# WeMos32Buttons.net
KiCad netlist of a schematic drawn in EAGLE
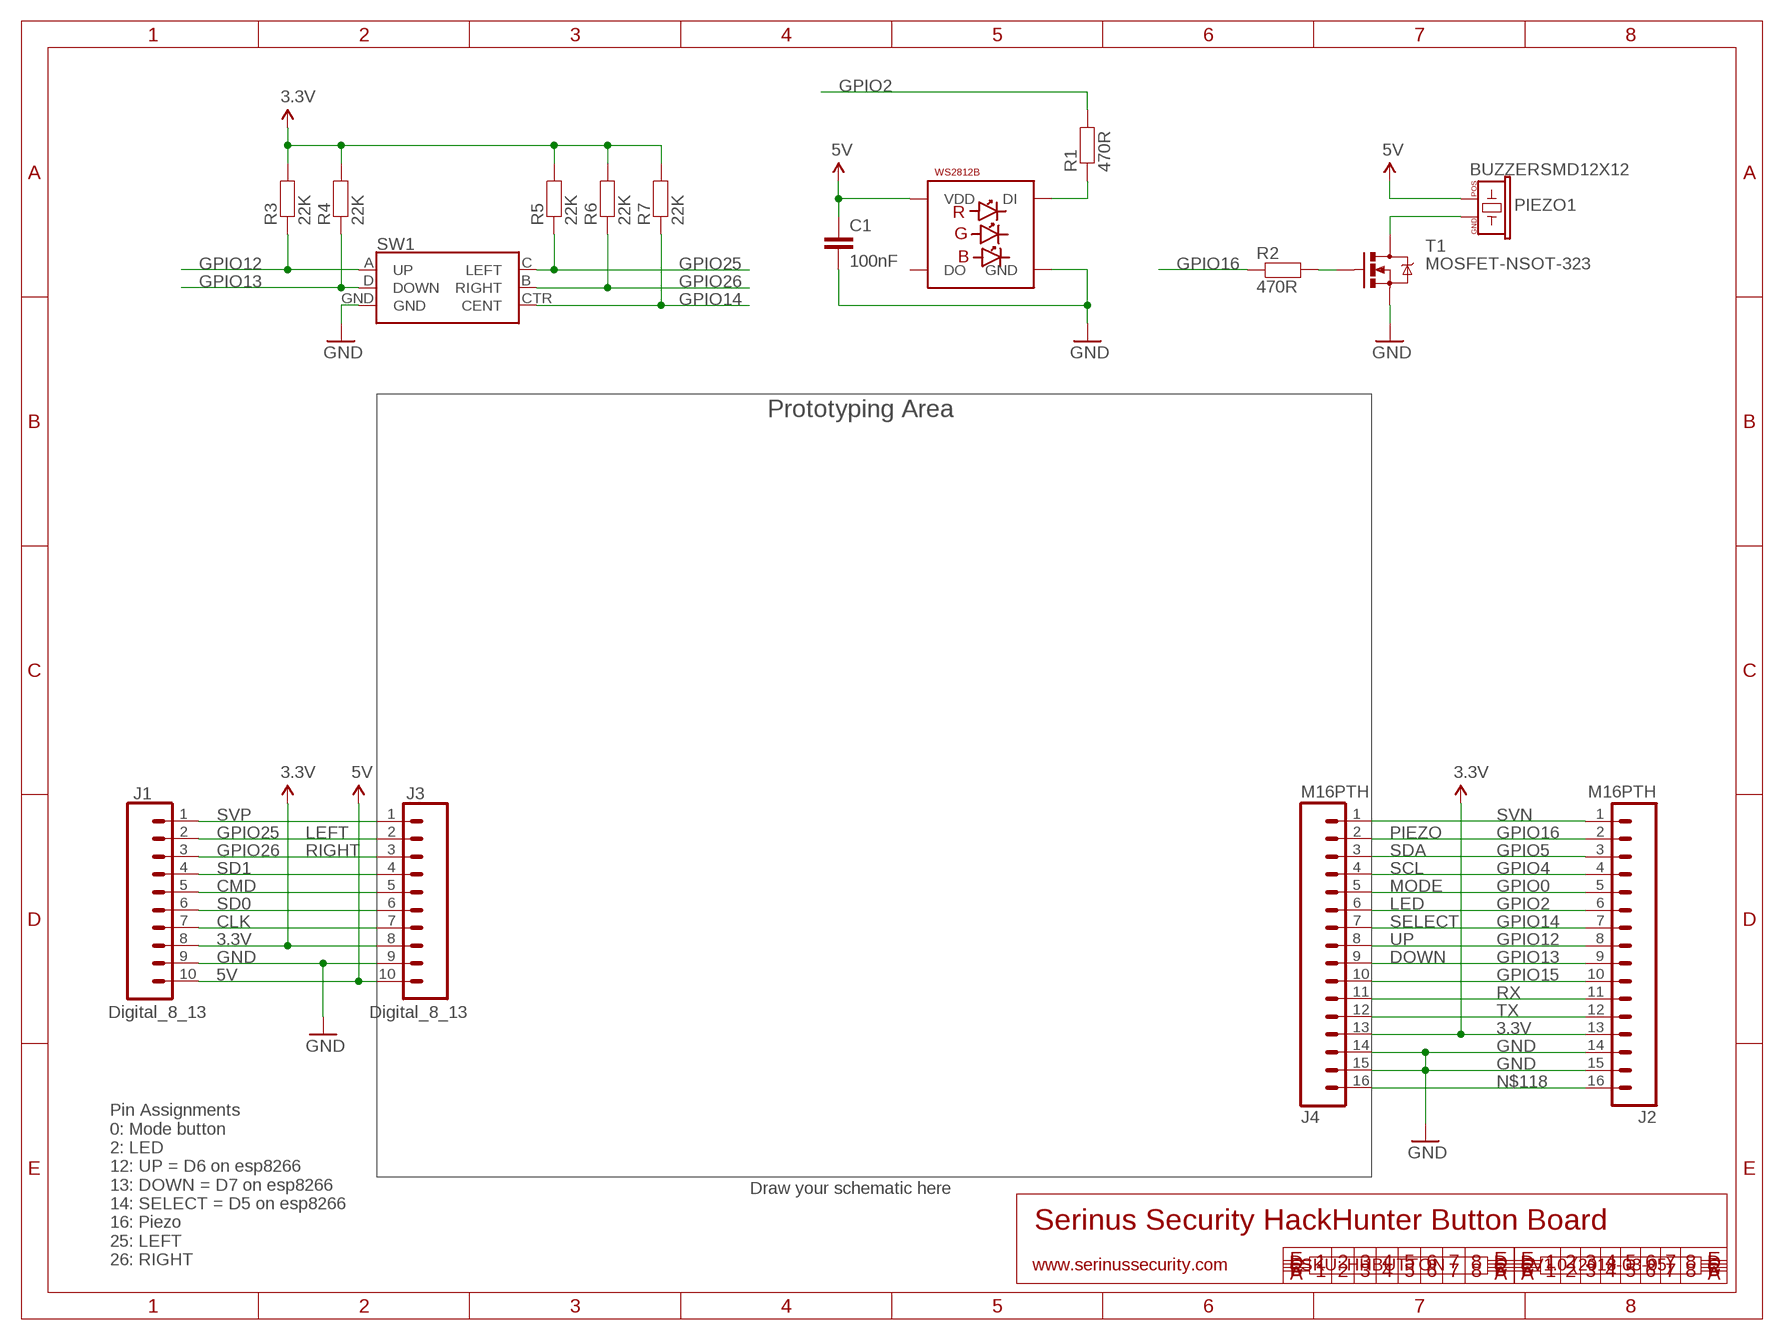
[diagram p0: schematic, sheet 1]

(export (version "E")
  (design (tool "Eeschema 10.0.6"))
  (components
    (comp (ref "C1")
      (value "100nF")
      (footprint "eagle-import:0603")
      (libsource (lib "eagle-import") (part "CAP0603"))
    )
    (comp (ref "J1")
      (value "Digital_8_13")
      (footprint "eagle-import:1X10")
      (libsource (lib "eagle-import") (part "M100.1"))
    )
    (comp (ref "J2")
      (value "M16PTH")
      (footprint "eagle-import:1X16")
      (libsource (lib "eagle-import") (part "M16PTH"))
    )
    (comp (ref "J3")
      (value "Digital_8_13")
      (footprint "eagle-import:1X10")
      (libsource (lib "eagle-import") (part "M100.1"))
    )
    (comp (ref "J4")
      (value "M16PTH")
      (footprint "eagle-import:1X16")
      (libsource (lib "eagle-import") (part "M16PTH"))
    )
    (comp (ref "LED2")
      (value "WS2812B5050")
      (footprint "eagle-import:WS2812B")
      (libsource (lib "eagle-import") (part "WS2812B5050"))
    )
    (comp (ref "PIEZO1")
      (value "BUZZERSMD12X12")
      (footprint "eagle-import:BUZZER-12X12-SMT")
      (libsource (lib "eagle-import") (part "BUZZERSMD12X12"))
    )
    (comp (ref "R1")
      (value "470R")
      (footprint "eagle-import:0603")
      (libsource (lib "eagle-import") (part "RESISTOR0603"))
    )
    (comp (ref "R2")
      (value "470R")
      (footprint "eagle-import:0603")
      (libsource (lib "eagle-import") (part "RESISTOR0603"))
    )
    (comp (ref "R3")
      (value "22K")
      (footprint "eagle-import:0603")
      (libsource (lib "eagle-import") (part "RESISTOR0603"))
    )
    (comp (ref "R4")
      (value "22K")
      (footprint "eagle-import:0603")
      (libsource (lib "eagle-import") (part "RESISTOR0603"))
    )
    (comp (ref "R5")
      (value "22K")
      (footprint "eagle-import:0603")
      (libsource (lib "eagle-import") (part "RESISTOR0603"))
    )
    (comp (ref "R6")
      (value "22K")
      (footprint "eagle-import:0603")
      (libsource (lib "eagle-import") (part "RESISTOR0603"))
    )
    (comp (ref "R7")
      (value "22K")
      (footprint "eagle-import:0603")
      (libsource (lib "eagle-import") (part "RESISTOR0603"))
    )
    (comp (ref "SW1")
      (value "JOYSTICK_MINI")
      (footprint "eagle-import:JOYSTICK_MINI")
      (libsource (lib "eagle-import") (part "JOYSTICK_MINI"))
    )
    (comp (ref "T1")
      (value "MOSFET-NSOT-323")
      (footprint "eagle-import:SOT32-3")
      (libsource (lib "eagle-import") (part "MOSFET-NSOT-323"))
    )
  )
  (nets
    (net (code "1") (name "/CLK") (class "Default")
      (node (ref "J1") (pin "7") (pinfunction "7_7") (pintype "passive"))
      (node (ref "J3") (pin "7") (pinfunction "7_7") (pintype "passive"))
    )
    (net (code "2") (name "/CMD") (class "Default")
      (node (ref "J1") (pin "5") (pinfunction "5_5") (pintype "passive"))
      (node (ref "J3") (pin "5") (pinfunction "5_5") (pintype "passive"))
    )
    (net (code "3") (name "/GPIO0") (class "Default")
      (node (ref "J2") (pin "5") (pinfunction "5_5") (pintype "passive"))
      (node (ref "J4") (pin "5") (pinfunction "5_5") (pintype "passive"))
    )
    (net (code "4") (name "/GPIO2") (class "Default")
      (node (ref "J2") (pin "6") (pinfunction "6_6") (pintype "passive"))
      (node (ref "J4") (pin "6") (pinfunction "6_6") (pintype "passive"))
      (node (ref "R1") (pin "2") (pinfunction "2_2") (pintype "passive"))
    )
    (net (code "5") (name "/GPIO4") (class "Default")
      (node (ref "J2") (pin "4") (pinfunction "4_4") (pintype "passive"))
      (node (ref "J4") (pin "4") (pinfunction "4_4") (pintype "passive"))
    )
    (net (code "6") (name "/GPIO5") (class "Default")
      (node (ref "J2") (pin "3") (pinfunction "3_3") (pintype "passive"))
      (node (ref "J4") (pin "3") (pinfunction "3_3") (pintype "passive"))
    )
    (net (code "7") (name "/GPIO12") (class "Default")
      (node (ref "J2") (pin "8") (pinfunction "8_8") (pintype "passive"))
      (node (ref "J4") (pin "8") (pinfunction "8_8") (pintype "passive"))
      (node (ref "R3") (pin "1") (pinfunction "1_1") (pintype "passive"))
      (node (ref "SW1") (pin "A") (pinfunction "UP_A") (pintype "bidirectional"))
    )
    (net (code "8") (name "/GPIO13") (class "Default")
      (node (ref "J2") (pin "9") (pinfunction "9_9") (pintype "passive"))
      (node (ref "J4") (pin "9") (pinfunction "9_9") (pintype "passive"))
      (node (ref "R4") (pin "1") (pinfunction "1_1") (pintype "passive"))
      (node (ref "SW1") (pin "D") (pinfunction "DOWN_D") (pintype "bidirectional"))
    )
    (net (code "9") (name "/GPIO14") (class "Default")
      (node (ref "J2") (pin "7") (pinfunction "7_7") (pintype "passive"))
      (node (ref "J4") (pin "7") (pinfunction "7_7") (pintype "passive"))
      (node (ref "R7") (pin "1") (pinfunction "1_1") (pintype "passive"))
      (node (ref "SW1") (pin "CTR") (pinfunction "CENT_CTR") (pintype "bidirectional"))
    )
    (net (code "10") (name "/GPIO15") (class "Default")
      (node (ref "J2") (pin "10") (pinfunction "10_10") (pintype "passive"))
      (node (ref "J4") (pin "10") (pinfunction "10_10") (pintype "passive"))
    )
    (net (code "11") (name "/GPIO16") (class "Default")
      (node (ref "J2") (pin "2") (pinfunction "2_2") (pintype "passive"))
      (node (ref "J4") (pin "2") (pinfunction "2_2") (pintype "passive"))
      (node (ref "R2") (pin "1") (pinfunction "1_1") (pintype "passive"))
    )
    (net (code "12") (name "/GPIO25") (class "Default")
      (node (ref "J1") (pin "2") (pinfunction "2_2") (pintype "passive"))
      (node (ref "J3") (pin "2") (pinfunction "2_2") (pintype "passive"))
      (node (ref "R5") (pin "1") (pinfunction "1_1") (pintype "passive"))
      (node (ref "SW1") (pin "C") (pinfunction "LEFT_C") (pintype "bidirectional"))
    )
    (net (code "13") (name "/GPIO26") (class "Default")
      (node (ref "J1") (pin "3") (pinfunction "3_3") (pintype "passive"))
      (node (ref "J3") (pin "3") (pinfunction "3_3") (pintype "passive"))
      (node (ref "R6") (pin "1") (pinfunction "1_1") (pintype "passive"))
      (node (ref "SW1") (pin "B") (pinfunction "RIGHT_B") (pintype "bidirectional"))
    )
    (net (code "14") (name "/N$118") (class "Default")
      (node (ref "J2") (pin "16") (pinfunction "16_16") (pintype "passive"))
      (node (ref "J4") (pin "16") (pinfunction "16_16") (pintype "passive"))
    )
    (net (code "15") (name "/RX") (class "Default")
      (node (ref "J2") (pin "11") (pinfunction "11_11") (pintype "passive"))
      (node (ref "J4") (pin "11") (pinfunction "11_11") (pintype "passive"))
    )
    (net (code "16") (name "/SD0") (class "Default")
      (node (ref "J1") (pin "6") (pinfunction "6_6") (pintype "passive"))
      (node (ref "J3") (pin "6") (pinfunction "6_6") (pintype "passive"))
    )
    (net (code "17") (name "/SD1") (class "Default")
      (node (ref "J1") (pin "4") (pinfunction "4_4") (pintype "passive"))
      (node (ref "J3") (pin "4") (pinfunction "4_4") (pintype "passive"))
    )
    (net (code "18") (name "/SVN") (class "Default")
      (node (ref "J2") (pin "1") (pinfunction "1_1") (pintype "passive"))
      (node (ref "J4") (pin "1") (pinfunction "1_1") (pintype "passive"))
    )
    (net (code "19") (name "/SVP") (class "Default")
      (node (ref "J1") (pin "1") (pinfunction "1_1") (pintype "passive"))
      (node (ref "J3") (pin "1") (pinfunction "1_1") (pintype "passive"))
    )
    (net (code "20") (name "/TX") (class "Default")
      (node (ref "J2") (pin "12") (pinfunction "12_12") (pintype "passive"))
      (node (ref "J4") (pin "12") (pinfunction "12_12") (pintype "passive"))
    )
    (net (code "21") (name "3.3V") (class "Default")
      (node (ref "J1") (pin "8") (pinfunction "8_8") (pintype "passive"))
      (node (ref "J2") (pin "13") (pinfunction "13_13") (pintype "passive"))
      (node (ref "J3") (pin "8") (pinfunction "8_8") (pintype "passive"))
      (node (ref "J4") (pin "13") (pinfunction "13_13") (pintype "passive"))
      (node (ref "R3") (pin "2") (pinfunction "2_2") (pintype "passive"))
      (node (ref "R4") (pin "2") (pinfunction "2_2") (pintype "passive"))
      (node (ref "R5") (pin "2") (pinfunction "2_2") (pintype "passive"))
      (node (ref "R6") (pin "2") (pinfunction "2_2") (pintype "passive"))
      (node (ref "R7") (pin "2") (pinfunction "2_2") (pintype "passive"))
    )
    (net (code "22") (name "5V") (class "Default")
      (node (ref "C1") (pin "1") (pinfunction "1_1") (pintype "passive"))
      (node (ref "J1") (pin "10") (pinfunction "10_10") (pintype "passive"))
      (node (ref "J3") (pin "10") (pinfunction "10_10") (pintype "passive"))
      (node (ref "LED2") (pin "1-VDD") (pinfunction "VDD_1-VDD") (pintype "power_in"))
      (node (ref "PIEZO1") (pin "2") (pinfunction "POS_2") (pintype "passive"))
    )
    (net (code "23") (name "GND") (class "Default")
      (node (ref "C1") (pin "2") (pinfunction "2_2") (pintype "passive"))
      (node (ref "J1") (pin "9") (pinfunction "9_9") (pintype "passive"))
      (node (ref "J2") (pin "14") (pinfunction "14_14") (pintype "passive"))
      (node (ref "J2") (pin "15") (pinfunction "15_15") (pintype "passive"))
      (node (ref "J3") (pin "9") (pinfunction "9_9") (pintype "passive"))
      (node (ref "J4") (pin "14") (pinfunction "14_14") (pintype "passive"))
      (node (ref "J4") (pin "15") (pinfunction "15_15") (pintype "passive"))
      (node (ref "LED2") (pin "3-GND") (pinfunction "GND_3-GND") (pintype "power_in"))
      (node (ref "SW1") (pin "GND") (pinfunction "GND_GND") (pintype "bidirectional"))
      (node (ref "T1") (pin "2") (pinfunction "S_2") (pintype "passive"))
    )
    (net (code "24") (name "Net-(LED2-DI)") (class "Default")
      (node (ref "LED2") (pin "4-DIN") (pinfunction "DI_4-DIN") (pintype "input"))
      (node (ref "R1") (pin "1") (pinfunction "1_1") (pintype "passive"))
    )
    (net (code "25") (name "Net-(PIEZO1-GND)") (class "Default")
      (node (ref "PIEZO1") (pin "1") (pinfunction "GND_1") (pintype "passive"))
      (node (ref "T1") (pin "3") (pinfunction "D_3") (pintype "passive"))
    )
    (net (code "26") (name "Net-(T1-G)") (class "Default")
      (node (ref "R2") (pin "2") (pinfunction "2_2") (pintype "passive"))
      (node (ref "T1") (pin "1") (pinfunction "G_1") (pintype "passive"))
    )
    (net (code "27") (name "unconnected-(LED2-DO-Pad2-DOUT)") (class "Default")
      (node (ref "LED2") (pin "2-DOUT") (pinfunction "DO_2-DOUT") (pintype "output"))
    )
  )
)
